# rotary-led-ring.net
KiCad netlist of a schematic drawn in Altium Designer
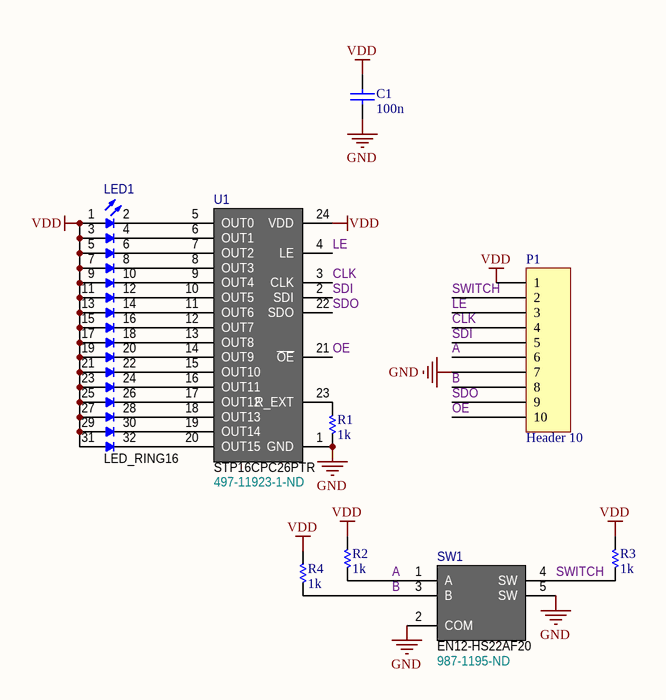
[diagram p0: rotary-led-ring.SchDoc]

(export (version "E")
  (design (tool "Eeschema 10.0.6"))
  (components
    (comp (ref "C1")
      (value "100n")
      (footprint "CAPC1608N")
      (description "Capacitor (Semiconductor SIM Model)")
      (fields (field (name "PUBLISHER") "Altium Limited"))
      (libsource (lib "Miscellaneous Devices") (part "Cap Semi"))
    )
    (comp (ref "LED1")
      (value "LED_RING16")
      (footprint "LEDRING_16_GREEN")
      (libsource (lib "LedRing") (part "LED_RING16"))
    )
    (comp (ref "P1")
      (value "Header 10")
      (footprint "HDR1X10")
      (description "Header, 10-Pin")
      (fields (field (name "PUBLISHER") "Altium Limited"))
      (libsource (lib "Miscellaneous Connectors") (part "Header 10"))
    )
    (comp (ref "R1")
      (value "1k")
      (footprint "RESC1608N")
      (description "Semiconductor Resistor")
      (fields (field (name "PUBLISHER") "Altium Limited"))
      (libsource (lib "Miscellaneous Devices") (part "Res Semi"))
    )
    (comp (ref "R2")
      (value "1k")
      (footprint "RESC1608N")
      (description "Semiconductor Resistor")
      (fields (field (name "PUBLISHER") "Altium Limited"))
      (libsource (lib "Miscellaneous Devices") (part "Res Semi"))
    )
    (comp (ref "R3")
      (value "1k")
      (footprint "RESC1608N")
      (description "Semiconductor Resistor")
      (fields (field (name "PUBLISHER") "Altium Limited"))
      (libsource (lib "Miscellaneous Devices") (part "Res Semi"))
    )
    (comp (ref "R4")
      (value "1k")
      (footprint "RESC1608N")
      (description "Semiconductor Resistor")
      (fields (field (name "PUBLISHER") "Altium Limited"))
      (libsource (lib "Miscellaneous Devices") (part "Res Semi"))
    )
    (comp (ref "SW1")
      (value "EN12-HS22AF20")
      (footprint "EN12-HS")
      (description "ENCODER 12MM ROTARY SW TOP ADJ")
      (fields
        (field (name "MANUFACTURER") "TT Electronics/BI")
        (field (name "SUPPLIER PART NUMBER 1") "987-1195-ND")
      )
      (libsource (lib "TT Encoders") (part "EN12-HS22AF20"))
    )
    (comp (ref "U1")
      (value "STP16CPC26PTR")
      (footprint "SOP635P600-24N")
      (description "IC LED DRVR LIN DIM 90MA 24QSOP")
      (fields
        (field (name "MANUFACTURER") "STMicroelectronics")
        (field (name "SUPPLIER PART NUMBER 1") "497-11923-1-ND")
      )
      (libsource (lib "ST LED Driver") (part "STP16CPC26PTR"))
    )
  )
  (nets
    (net (code "1") (name "/A") (class "Default")
      (node (ref "P1") (pin "6") (pinfunction "6_6") (pintype "passive"))
      (node (ref "R2") (pin "2") (pinfunction "2_2") (pintype "passive"))
      (node (ref "SW1") (pin "1") (pinfunction "A_1") (pintype "power_in"))
    )
    (net (code "2") (name "/B") (class "Default")
      (node (ref "P1") (pin "8") (pinfunction "8_8") (pintype "passive"))
      (node (ref "R4") (pin "2") (pinfunction "2_2") (pintype "passive"))
      (node (ref "SW1") (pin "3") (pinfunction "B_3") (pintype "power_in"))
    )
    (net (code "3") (name "/CLK") (class "Default")
      (node (ref "P1") (pin "4") (pinfunction "4_4") (pintype "passive"))
      (node (ref "U1") (pin "3") (pinfunction "CLK_3") (pintype "power_in"))
    )
    (net (code "4") (name "/LE") (class "Default")
      (node (ref "P1") (pin "3") (pinfunction "3_3") (pintype "passive"))
      (node (ref "U1") (pin "4") (pinfunction "LE_4") (pintype "power_in"))
    )
    (net (code "5") (name "/OE") (class "Default")
      (node (ref "P1") (pin "10") (pinfunction "10_10") (pintype "passive"))
      (node (ref "U1") (pin "21") (pinfunction "~{OE}_21") (pintype "power_in"))
    )
    (net (code "6") (name "/SDI") (class "Default")
      (node (ref "P1") (pin "5") (pinfunction "5_5") (pintype "passive"))
      (node (ref "U1") (pin "2") (pinfunction "SDI_2") (pintype "power_in"))
    )
    (net (code "7") (name "/SDO") (class "Default")
      (node (ref "P1") (pin "9") (pinfunction "9_9") (pintype "passive"))
      (node (ref "U1") (pin "22") (pinfunction "SDO_22") (pintype "power_in"))
    )
    (net (code "8") (name "/SWITCH") (class "Default")
      (node (ref "P1") (pin "2") (pinfunction "2_2") (pintype "passive"))
      (node (ref "R3") (pin "2") (pinfunction "2_2") (pintype "passive"))
      (node (ref "SW1") (pin "4") (pinfunction "SW_4") (pintype "power_in"))
    )
    (net (code "9") (name "GND") (class "Default")
      (node (ref "C1") (pin "1") (pinfunction "1_1") (pintype "passive"))
      (node (ref "P1") (pin "7") (pinfunction "7_7") (pintype "passive"))
      (node (ref "R1") (pin "2") (pinfunction "2_2") (pintype "passive"))
      (node (ref "SW1") (pin "2") (pinfunction "COM_2") (pintype "power_in"))
      (node (ref "SW1") (pin "5") (pinfunction "SW_5") (pintype "power_in"))
      (node (ref "U1") (pin "1") (pinfunction "GND_1") (pintype "power_in"))
    )
    (net (code "10") (name "Net-(U1-OUT0)") (class "Default")
      (node (ref "LED1") (pin "2") (pinfunction "K_2") (pintype "power_in"))
      (node (ref "U1") (pin "5") (pinfunction "OUT0_5") (pintype "power_in"))
    )
    (net (code "11") (name "Net-(U1-OUT1)") (class "Default")
      (node (ref "LED1") (pin "4") (pinfunction "K_4") (pintype "power_in"))
      (node (ref "U1") (pin "6") (pinfunction "OUT1_6") (pintype "power_in"))
    )
    (net (code "12") (name "Net-(U1-OUT2)") (class "Default")
      (node (ref "LED1") (pin "6") (pinfunction "K_6") (pintype "power_in"))
      (node (ref "U1") (pin "7") (pinfunction "OUT2_7") (pintype "power_in"))
    )
    (net (code "13") (name "Net-(U1-OUT3)") (class "Default")
      (node (ref "LED1") (pin "8") (pinfunction "K_8") (pintype "power_in"))
      (node (ref "U1") (pin "8") (pinfunction "OUT3_8") (pintype "power_in"))
    )
    (net (code "14") (name "Net-(U1-OUT4)") (class "Default")
      (node (ref "LED1") (pin "10") (pinfunction "K_10") (pintype "power_in"))
      (node (ref "U1") (pin "9") (pinfunction "OUT4_9") (pintype "power_in"))
    )
    (net (code "15") (name "Net-(U1-OUT5)") (class "Default")
      (node (ref "LED1") (pin "12") (pinfunction "K_12") (pintype "power_in"))
      (node (ref "U1") (pin "10") (pinfunction "OUT5_10") (pintype "power_in"))
    )
    (net (code "16") (name "Net-(U1-OUT6)") (class "Default")
      (node (ref "LED1") (pin "14") (pinfunction "K_14") (pintype "power_in"))
      (node (ref "U1") (pin "11") (pinfunction "OUT6_11") (pintype "power_in"))
    )
    (net (code "17") (name "Net-(U1-OUT7)") (class "Default")
      (node (ref "LED1") (pin "16") (pinfunction "K_16") (pintype "power_in"))
      (node (ref "U1") (pin "12") (pinfunction "OUT7_12") (pintype "power_in"))
    )
    (net (code "18") (name "Net-(U1-OUT8)") (class "Default")
      (node (ref "LED1") (pin "18") (pinfunction "K_18") (pintype "power_in"))
      (node (ref "U1") (pin "13") (pinfunction "OUT8_13") (pintype "power_in"))
    )
    (net (code "19") (name "Net-(U1-OUT9)") (class "Default")
      (node (ref "LED1") (pin "20") (pinfunction "K_20") (pintype "power_in"))
      (node (ref "U1") (pin "14") (pinfunction "OUT9_14") (pintype "power_in"))
    )
    (net (code "20") (name "Net-(U1-OUT10)") (class "Default")
      (node (ref "LED1") (pin "22") (pinfunction "K_22") (pintype "power_in"))
      (node (ref "U1") (pin "15") (pinfunction "OUT10_15") (pintype "power_in"))
    )
    (net (code "21") (name "Net-(U1-OUT11)") (class "Default")
      (node (ref "LED1") (pin "24") (pinfunction "K_24") (pintype "power_in"))
      (node (ref "U1") (pin "16") (pinfunction "OUT11_16") (pintype "power_in"))
    )
    (net (code "22") (name "Net-(U1-OUT12)") (class "Default")
      (node (ref "LED1") (pin "26") (pinfunction "K_26") (pintype "power_in"))
      (node (ref "U1") (pin "17") (pinfunction "OUT12_17") (pintype "power_in"))
    )
    (net (code "23") (name "Net-(U1-OUT13)") (class "Default")
      (node (ref "LED1") (pin "28") (pinfunction "K_28") (pintype "power_in"))
      (node (ref "U1") (pin "18") (pinfunction "OUT13_18") (pintype "power_in"))
    )
    (net (code "24") (name "Net-(U1-OUT14)") (class "Default")
      (node (ref "LED1") (pin "30") (pinfunction "K_30") (pintype "power_in"))
      (node (ref "U1") (pin "19") (pinfunction "OUT14_19") (pintype "power_in"))
    )
    (net (code "25") (name "Net-(U1-OUT15)") (class "Default")
      (node (ref "LED1") (pin "32") (pinfunction "K_32") (pintype "power_in"))
      (node (ref "U1") (pin "20") (pinfunction "OUT15_20") (pintype "power_in"))
    )
    (net (code "26") (name "Net-(U1-R_EXT)") (class "Default")
      (node (ref "R1") (pin "1") (pinfunction "1_1") (pintype "passive"))
      (node (ref "U1") (pin "23") (pinfunction "R_EXT_23") (pintype "power_in"))
    )
    (net (code "27") (name "VDD") (class "Default")
      (node (ref "C1") (pin "2") (pinfunction "2_2") (pintype "passive"))
      (node (ref "LED1") (pin "1") (pinfunction "A_1") (pintype "power_in"))
      (node (ref "LED1") (pin "11") (pinfunction "A_11") (pintype "power_in"))
      (node (ref "LED1") (pin "13") (pinfunction "A_13") (pintype "power_in"))
      (node (ref "LED1") (pin "15") (pinfunction "A_15") (pintype "power_in"))
      (node (ref "LED1") (pin "17") (pinfunction "A_17") (pintype "power_in"))
      (node (ref "LED1") (pin "19") (pinfunction "A_19") (pintype "power_in"))
      (node (ref "LED1") (pin "21") (pinfunction "A_21") (pintype "power_in"))
      (node (ref "LED1") (pin "23") (pinfunction "A_23") (pintype "power_in"))
      (node (ref "LED1") (pin "25") (pinfunction "A_25") (pintype "power_in"))
      (node (ref "LED1") (pin "27") (pinfunction "A_27") (pintype "power_in"))
      (node (ref "LED1") (pin "29") (pinfunction "A_29") (pintype "power_in"))
      (node (ref "LED1") (pin "3") (pinfunction "A_3") (pintype "power_in"))
      (node (ref "LED1") (pin "31") (pinfunction "A_31") (pintype "power_in"))
      (node (ref "LED1") (pin "5") (pinfunction "A_5") (pintype "power_in"))
      (node (ref "LED1") (pin "7") (pinfunction "A_7") (pintype "power_in"))
      (node (ref "LED1") (pin "9") (pinfunction "A_9") (pintype "power_in"))
      (node (ref "P1") (pin "1") (pinfunction "1_1") (pintype "passive"))
      (node (ref "R2") (pin "1") (pinfunction "1_1") (pintype "passive"))
      (node (ref "R3") (pin "1") (pinfunction "1_1") (pintype "passive"))
      (node (ref "R4") (pin "1") (pinfunction "1_1") (pintype "passive"))
      (node (ref "U1") (pin "24") (pinfunction "VDD_24") (pintype "power_in"))
    )
  )
)
